# Sheet4.net
KiCad netlist of a schematic drawn in Altium Designer
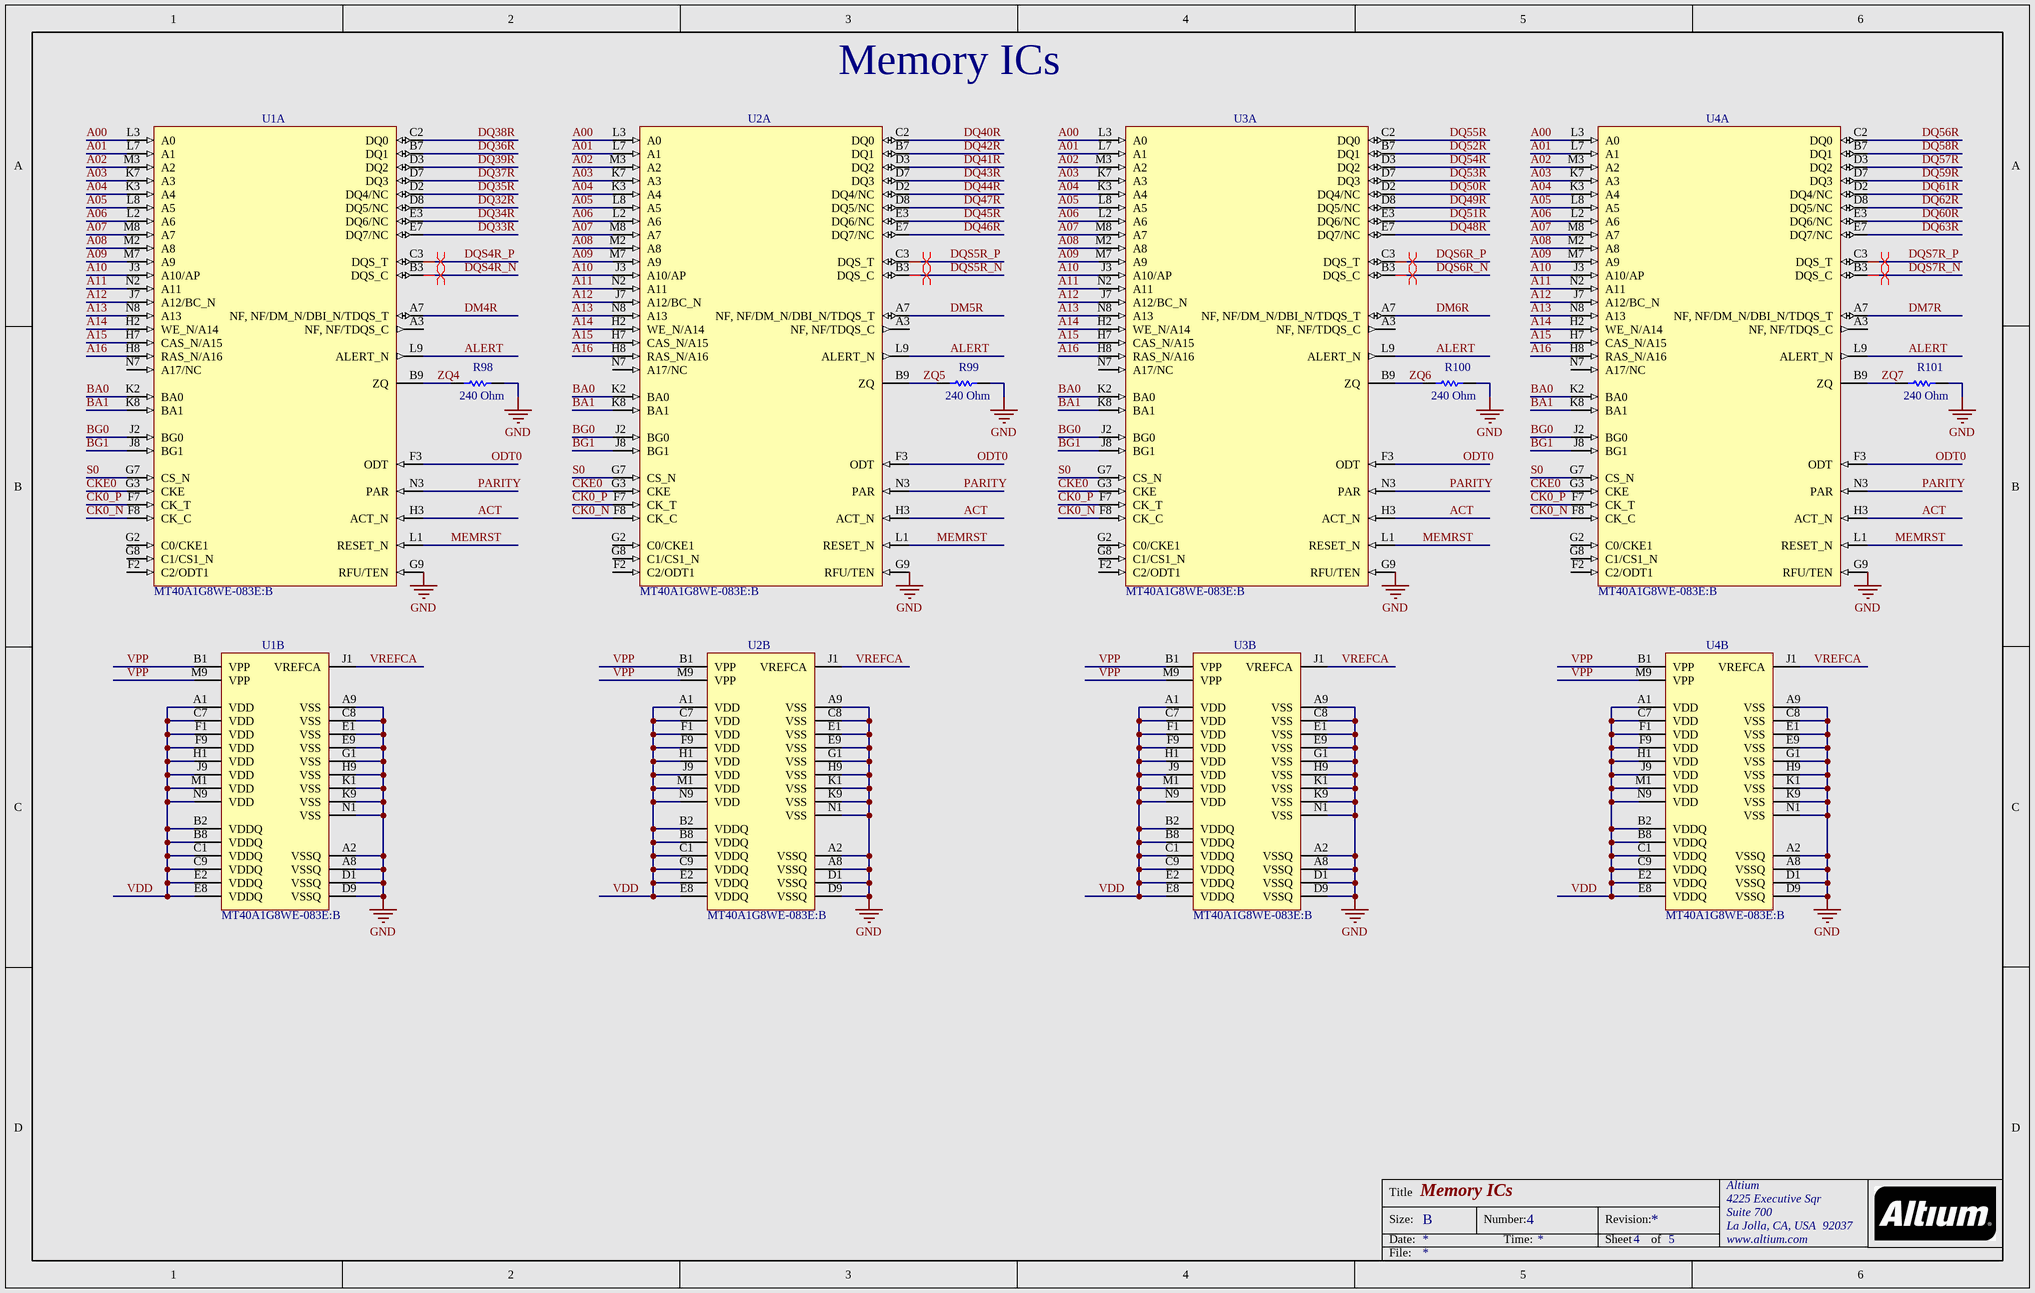
[diagram p0: Sheet4.SchDoc]

(export (version "E")
  (design (tool "Eeschema 10.0.6"))
  (components
    (comp (ref "R98")
      (value "ERJ-2GEJ241x")
      (footprint "RESC1005X40X25ML05T05")
      (description "Chip Resistor, 240 Ohm, +/- 5%, 100 mW, -55 to 155 degC, 0402 (1005 Metric), RoHS, Tape and Reel")
      (fields
        (field (name "RESISTANCE") "240 Ohm")
        (field (name "TOLERANCE") "5%")
        (field (name "MANUFACTURER") "Basic Passives")
      )
      (libsource (lib "Altium Content Vault") (part "CMP-2002-00493-3"))
    )
    (comp (ref "R99")
      (value "ERJ-2GEJ241x")
      (footprint "RESC1005X40X25ML05T05")
      (description "Chip Resistor, 240 Ohm, +/- 5%, 100 mW, -55 to 155 degC, 0402 (1005 Metric), RoHS, Tape and Reel")
      (fields
        (field (name "RESISTANCE") "240 Ohm")
        (field (name "TOLERANCE") "5%")
        (field (name "MANUFACTURER") "Basic Passives")
      )
      (libsource (lib "Altium Content Vault") (part "CMP-2002-00493-3"))
    )
    (comp (ref "R100")
      (value "ERJ-2GEJ241x")
      (footprint "RESC1005X40X25ML05T05")
      (description "Chip Resistor, 240 Ohm, +/- 5%, 100 mW, -55 to 155 degC, 0402 (1005 Metric), RoHS, Tape and Reel")
      (fields
        (field (name "RESISTANCE") "240 Ohm")
        (field (name "TOLERANCE") "5%")
        (field (name "MANUFACTURER") "Basic Passives")
      )
      (libsource (lib "Altium Content Vault") (part "CMP-2002-00493-3"))
    )
    (comp (ref "R101")
      (value "ERJ-2GEJ241x")
      (footprint "RESC1005X40X25ML05T05")
      (description "Chip Resistor, 240 Ohm, +/- 5%, 100 mW, -55 to 155 degC, 0402 (1005 Metric), RoHS, Tape and Reel")
      (fields
        (field (name "RESISTANCE") "240 Ohm")
        (field (name "TOLERANCE") "5%")
        (field (name "MANUFACTURER") "Basic Passives")
      )
      (libsource (lib "Altium Content Vault") (part "CMP-2002-00493-3"))
    )
    (comp (ref "U1")
      (value "MT40A1G8WE-083E:B")
      (footprint "MICT-WE-78")
      (description "8 Gb DDR4 SDRAM, 1 Gig x 8, 1.2 V, 0 to 95 degC, 78-Ball FBGA (WE), RoHS")
      (libsource (lib "Altium Content Vault") (part "CMP-1738-00001-1"))
    )
    (comp (ref "U2")
      (value "MT40A1G8WE-083E:B")
      (footprint "MICT-WE-78")
      (description "8 Gb DDR4 SDRAM, 1 Gig x 8, 1.2 V, 0 to 95 degC, 78-Ball FBGA (WE), RoHS")
      (libsource (lib "Altium Content Vault") (part "CMP-1738-00001-1"))
    )
    (comp (ref "U3")
      (value "MT40A1G8WE-083E:B")
      (footprint "MICT-WE-78")
      (description "8 Gb DDR4 SDRAM, 1 Gig x 8, 1.2 V, 0 to 95 degC, 78-Ball FBGA (WE), RoHS")
      (libsource (lib "Altium Content Vault") (part "CMP-1738-00001-1"))
    )
    (comp (ref "U4")
      (value "MT40A1G8WE-083E:B")
      (footprint "MICT-WE-78")
      (description "8 Gb DDR4 SDRAM, 1 Gig x 8, 1.2 V, 0 to 95 degC, 78-Ball FBGA (WE), RoHS")
      (libsource (lib "Altium Content Vault") (part "CMP-1738-00001-1"))
    )
  )
  (nets
    (net (code "1") (name "/A00") (class "Default")
      (node (ref "U1") (pin "L3") (pinfunction "A0_L3") (pintype "input"))
      (node (ref "U2") (pin "L3") (pinfunction "A0_L3") (pintype "input"))
      (node (ref "U3") (pin "L3") (pinfunction "A0_L3") (pintype "input"))
      (node (ref "U4") (pin "L3") (pinfunction "A0_L3") (pintype "input"))
    )
    (net (code "2") (name "/A01") (class "Default")
      (node (ref "U1") (pin "L7") (pinfunction "A1_L7") (pintype "input"))
      (node (ref "U2") (pin "L7") (pinfunction "A1_L7") (pintype "input"))
      (node (ref "U3") (pin "L7") (pinfunction "A1_L7") (pintype "input"))
      (node (ref "U4") (pin "L7") (pinfunction "A1_L7") (pintype "input"))
    )
    (net (code "3") (name "/A02") (class "Default")
      (node (ref "U1") (pin "M3") (pinfunction "A2_M3") (pintype "input"))
      (node (ref "U2") (pin "M3") (pinfunction "A2_M3") (pintype "input"))
      (node (ref "U3") (pin "M3") (pinfunction "A2_M3") (pintype "input"))
      (node (ref "U4") (pin "M3") (pinfunction "A2_M3") (pintype "input"))
    )
    (net (code "4") (name "/A03") (class "Default")
      (node (ref "U1") (pin "K7") (pinfunction "A3_K7") (pintype "input"))
      (node (ref "U2") (pin "K7") (pinfunction "A3_K7") (pintype "input"))
      (node (ref "U3") (pin "K7") (pinfunction "A3_K7") (pintype "input"))
      (node (ref "U4") (pin "K7") (pinfunction "A3_K7") (pintype "input"))
    )
    (net (code "5") (name "/A04") (class "Default")
      (node (ref "U1") (pin "K3") (pinfunction "A4_K3") (pintype "input"))
      (node (ref "U2") (pin "K3") (pinfunction "A4_K3") (pintype "input"))
      (node (ref "U3") (pin "K3") (pinfunction "A4_K3") (pintype "input"))
      (node (ref "U4") (pin "K3") (pinfunction "A4_K3") (pintype "input"))
    )
    (net (code "6") (name "/A05") (class "Default")
      (node (ref "U1") (pin "L8") (pinfunction "A5_L8") (pintype "input"))
      (node (ref "U2") (pin "L8") (pinfunction "A5_L8") (pintype "input"))
      (node (ref "U3") (pin "L8") (pinfunction "A5_L8") (pintype "input"))
      (node (ref "U4") (pin "L8") (pinfunction "A5_L8") (pintype "input"))
    )
    (net (code "7") (name "/A06") (class "Default")
      (node (ref "U1") (pin "L2") (pinfunction "A6_L2") (pintype "input"))
      (node (ref "U2") (pin "L2") (pinfunction "A6_L2") (pintype "input"))
      (node (ref "U3") (pin "L2") (pinfunction "A6_L2") (pintype "input"))
      (node (ref "U4") (pin "L2") (pinfunction "A6_L2") (pintype "input"))
    )
    (net (code "8") (name "/A07") (class "Default")
      (node (ref "U1") (pin "M8") (pinfunction "A7_M8") (pintype "input"))
      (node (ref "U2") (pin "M8") (pinfunction "A7_M8") (pintype "input"))
      (node (ref "U3") (pin "M8") (pinfunction "A7_M8") (pintype "input"))
      (node (ref "U4") (pin "M8") (pinfunction "A7_M8") (pintype "input"))
    )
    (net (code "9") (name "/A08") (class "Default")
      (node (ref "U1") (pin "M2") (pinfunction "A8_M2") (pintype "input"))
      (node (ref "U2") (pin "M2") (pinfunction "A8_M2") (pintype "input"))
      (node (ref "U3") (pin "M2") (pinfunction "A8_M2") (pintype "input"))
      (node (ref "U4") (pin "M2") (pinfunction "A8_M2") (pintype "input"))
    )
    (net (code "10") (name "/A09") (class "Default")
      (node (ref "U1") (pin "M7") (pinfunction "A9_M7") (pintype "input"))
      (node (ref "U2") (pin "M7") (pinfunction "A9_M7") (pintype "input"))
      (node (ref "U3") (pin "M7") (pinfunction "A9_M7") (pintype "input"))
      (node (ref "U4") (pin "M7") (pinfunction "A9_M7") (pintype "input"))
    )
    (net (code "11") (name "/A10") (class "Default")
      (node (ref "U1") (pin "J3") (pinfunction "A10/AP_J3") (pintype "input"))
      (node (ref "U2") (pin "J3") (pinfunction "A10/AP_J3") (pintype "input"))
      (node (ref "U3") (pin "J3") (pinfunction "A10/AP_J3") (pintype "input"))
      (node (ref "U4") (pin "J3") (pinfunction "A10/AP_J3") (pintype "input"))
    )
    (net (code "12") (name "/A11") (class "Default")
      (node (ref "U1") (pin "N2") (pinfunction "A11_N2") (pintype "input"))
      (node (ref "U2") (pin "N2") (pinfunction "A11_N2") (pintype "input"))
      (node (ref "U3") (pin "N2") (pinfunction "A11_N2") (pintype "input"))
      (node (ref "U4") (pin "N2") (pinfunction "A11_N2") (pintype "input"))
    )
    (net (code "13") (name "/A12") (class "Default")
      (node (ref "U1") (pin "J7") (pinfunction "A12/BC_N_J7") (pintype "input"))
      (node (ref "U2") (pin "J7") (pinfunction "A12/BC_N_J7") (pintype "input"))
      (node (ref "U3") (pin "J7") (pinfunction "A12/BC_N_J7") (pintype "input"))
      (node (ref "U4") (pin "J7") (pinfunction "A12/BC_N_J7") (pintype "input"))
    )
    (net (code "14") (name "/A13") (class "Default")
      (node (ref "U1") (pin "N8") (pinfunction "A13_N8") (pintype "input"))
      (node (ref "U2") (pin "N8") (pinfunction "A13_N8") (pintype "input"))
      (node (ref "U3") (pin "N8") (pinfunction "A13_N8") (pintype "input"))
      (node (ref "U4") (pin "N8") (pinfunction "A13_N8") (pintype "input"))
    )
    (net (code "15") (name "/A14") (class "Default")
      (node (ref "U1") (pin "H2") (pinfunction "WE_N/A14_H2") (pintype "input"))
      (node (ref "U2") (pin "H2") (pinfunction "WE_N/A14_H2") (pintype "input"))
      (node (ref "U3") (pin "H2") (pinfunction "WE_N/A14_H2") (pintype "input"))
      (node (ref "U4") (pin "H2") (pinfunction "WE_N/A14_H2") (pintype "input"))
    )
    (net (code "16") (name "/A15") (class "Default")
      (node (ref "U1") (pin "H7") (pinfunction "CAS_N/A15_H7") (pintype "input"))
      (node (ref "U2") (pin "H7") (pinfunction "CAS_N/A15_H7") (pintype "input"))
      (node (ref "U3") (pin "H7") (pinfunction "CAS_N/A15_H7") (pintype "input"))
      (node (ref "U4") (pin "H7") (pinfunction "CAS_N/A15_H7") (pintype "input"))
    )
    (net (code "17") (name "/A16") (class "Default")
      (node (ref "U1") (pin "H8") (pinfunction "RAS_N/A16_H8") (pintype "input"))
      (node (ref "U2") (pin "H8") (pinfunction "RAS_N/A16_H8") (pintype "input"))
      (node (ref "U3") (pin "H8") (pinfunction "RAS_N/A16_H8") (pintype "input"))
      (node (ref "U4") (pin "H8") (pinfunction "RAS_N/A16_H8") (pintype "input"))
    )
    (net (code "18") (name "/ACT") (class "Default")
      (node (ref "U1") (pin "H3") (pinfunction "ACT_N_H3") (pintype "input"))
      (node (ref "U2") (pin "H3") (pinfunction "ACT_N_H3") (pintype "input"))
      (node (ref "U3") (pin "H3") (pinfunction "ACT_N_H3") (pintype "input"))
      (node (ref "U4") (pin "H3") (pinfunction "ACT_N_H3") (pintype "input"))
    )
    (net (code "19") (name "/ALERT") (class "Default")
      (node (ref "U1") (pin "L9") (pinfunction "ALERT_N_L9") (pintype "output"))
      (node (ref "U2") (pin "L9") (pinfunction "ALERT_N_L9") (pintype "output"))
      (node (ref "U3") (pin "L9") (pinfunction "ALERT_N_L9") (pintype "output"))
      (node (ref "U4") (pin "L9") (pinfunction "ALERT_N_L9") (pintype "output"))
    )
    (net (code "20") (name "/BA0") (class "Default")
      (node (ref "U1") (pin "K2") (pinfunction "BA0_K2") (pintype "input"))
      (node (ref "U2") (pin "K2") (pinfunction "BA0_K2") (pintype "input"))
      (node (ref "U3") (pin "K2") (pinfunction "BA0_K2") (pintype "input"))
      (node (ref "U4") (pin "K2") (pinfunction "BA0_K2") (pintype "input"))
    )
    (net (code "21") (name "/BA1") (class "Default")
      (node (ref "U1") (pin "K8") (pinfunction "BA1_K8") (pintype "input"))
      (node (ref "U2") (pin "K8") (pinfunction "BA1_K8") (pintype "input"))
      (node (ref "U3") (pin "K8") (pinfunction "BA1_K8") (pintype "input"))
      (node (ref "U4") (pin "K8") (pinfunction "BA1_K8") (pintype "input"))
    )
    (net (code "22") (name "/BG0") (class "Default")
      (node (ref "U1") (pin "J2") (pinfunction "BG0_J2") (pintype "input"))
      (node (ref "U2") (pin "J2") (pinfunction "BG0_J2") (pintype "input"))
      (node (ref "U3") (pin "J2") (pinfunction "BG0_J2") (pintype "input"))
      (node (ref "U4") (pin "J2") (pinfunction "BG0_J2") (pintype "input"))
    )
    (net (code "23") (name "/BG1") (class "Default")
      (node (ref "U1") (pin "J8") (pinfunction "BG1_J8") (pintype "input"))
      (node (ref "U2") (pin "J8") (pinfunction "BG1_J8") (pintype "input"))
      (node (ref "U3") (pin "J8") (pinfunction "BG1_J8") (pintype "input"))
      (node (ref "U4") (pin "J8") (pinfunction "BG1_J8") (pintype "input"))
    )
    (net (code "24") (name "/CK0_N") (class "Default")
      (node (ref "U1") (pin "F8") (pinfunction "CK_C_F8") (pintype "input"))
      (node (ref "U2") (pin "F8") (pinfunction "CK_C_F8") (pintype "input"))
      (node (ref "U3") (pin "F8") (pinfunction "CK_C_F8") (pintype "input"))
      (node (ref "U4") (pin "F8") (pinfunction "CK_C_F8") (pintype "input"))
    )
    (net (code "25") (name "/CK0_P") (class "Default")
      (node (ref "U1") (pin "F7") (pinfunction "CK_T_F7") (pintype "input"))
      (node (ref "U2") (pin "F7") (pinfunction "CK_T_F7") (pintype "input"))
      (node (ref "U3") (pin "F7") (pinfunction "CK_T_F7") (pintype "input"))
      (node (ref "U4") (pin "F7") (pinfunction "CK_T_F7") (pintype "input"))
    )
    (net (code "26") (name "/CKE0") (class "Default")
      (node (ref "U1") (pin "G3") (pinfunction "CKE_G3") (pintype "input"))
      (node (ref "U2") (pin "G3") (pinfunction "CKE_G3") (pintype "input"))
      (node (ref "U3") (pin "G3") (pinfunction "CKE_G3") (pintype "input"))
      (node (ref "U4") (pin "G3") (pinfunction "CKE_G3") (pintype "input"))
    )
    (net (code "27") (name "/DM4R") (class "Default")
      (node (ref "U1") (pin "A7") (pinfunction "NF,_NF/DM_N/DBI_N/TDQS_T_A7") (pintype "bidirectional"))
    )
    (net (code "28") (name "/DM5R") (class "Default")
      (node (ref "U2") (pin "A7") (pinfunction "NF,_NF/DM_N/DBI_N/TDQS_T_A7") (pintype "bidirectional"))
    )
    (net (code "29") (name "/DM6R") (class "Default")
      (node (ref "U3") (pin "A7") (pinfunction "NF,_NF/DM_N/DBI_N/TDQS_T_A7") (pintype "bidirectional"))
    )
    (net (code "30") (name "/DM7R") (class "Default")
      (node (ref "U4") (pin "A7") (pinfunction "NF,_NF/DM_N/DBI_N/TDQS_T_A7") (pintype "bidirectional"))
    )
    (net (code "31") (name "/DQ32R") (class "Default")
      (node (ref "U1") (pin "D8") (pinfunction "DQ5/NC_D8") (pintype "bidirectional"))
    )
    (net (code "32") (name "/DQ33R") (class "Default")
      (node (ref "U1") (pin "E7") (pinfunction "DQ7/NC_E7") (pintype "bidirectional"))
    )
    (net (code "33") (name "/DQ34R") (class "Default")
      (node (ref "U1") (pin "E3") (pinfunction "DQ6/NC_E3") (pintype "bidirectional"))
    )
    (net (code "34") (name "/DQ35R") (class "Default")
      (node (ref "U1") (pin "D2") (pinfunction "DQ4/NC_D2") (pintype "bidirectional"))
    )
    (net (code "35") (name "/DQ36R") (class "Default")
      (node (ref "U1") (pin "B7") (pinfunction "DQ1_B7") (pintype "bidirectional"))
    )
    (net (code "36") (name "/DQ37R") (class "Default")
      (node (ref "U1") (pin "D7") (pinfunction "DQ3_D7") (pintype "bidirectional"))
    )
    (net (code "37") (name "/DQ38R") (class "Default")
      (node (ref "U1") (pin "C2") (pinfunction "DQ0_C2") (pintype "bidirectional"))
    )
    (net (code "38") (name "/DQ39R") (class "Default")
      (node (ref "U1") (pin "D3") (pinfunction "DQ2_D3") (pintype "bidirectional"))
    )
    (net (code "39") (name "/DQ40R") (class "Default")
      (node (ref "U2") (pin "C2") (pinfunction "DQ0_C2") (pintype "bidirectional"))
    )
    (net (code "40") (name "/DQ41R") (class "Default")
      (node (ref "U2") (pin "D3") (pinfunction "DQ2_D3") (pintype "bidirectional"))
    )
    (net (code "41") (name "/DQ42R") (class "Default")
      (node (ref "U2") (pin "B7") (pinfunction "DQ1_B7") (pintype "bidirectional"))
    )
    (net (code "42") (name "/DQ43R") (class "Default")
      (node (ref "U2") (pin "D7") (pinfunction "DQ3_D7") (pintype "bidirectional"))
    )
    (net (code "43") (name "/DQ44R") (class "Default")
      (node (ref "U2") (pin "D2") (pinfunction "DQ4/NC_D2") (pintype "bidirectional"))
    )
    (net (code "44") (name "/DQ45R") (class "Default")
      (node (ref "U2") (pin "E3") (pinfunction "DQ6/NC_E3") (pintype "bidirectional"))
    )
    (net (code "45") (name "/DQ46R") (class "Default")
      (node (ref "U2") (pin "E7") (pinfunction "DQ7/NC_E7") (pintype "bidirectional"))
    )
    (net (code "46") (name "/DQ47R") (class "Default")
      (node (ref "U2") (pin "D8") (pinfunction "DQ5/NC_D8") (pintype "bidirectional"))
    )
    (net (code "47") (name "/DQ48R") (class "Default")
      (node (ref "U3") (pin "E7") (pinfunction "DQ7/NC_E7") (pintype "bidirectional"))
    )
    (net (code "48") (name "/DQ49R") (class "Default")
      (node (ref "U3") (pin "D8") (pinfunction "DQ5/NC_D8") (pintype "bidirectional"))
    )
    (net (code "49") (name "/DQ50R") (class "Default")
      (node (ref "U3") (pin "D2") (pinfunction "DQ4/NC_D2") (pintype "bidirectional"))
    )
    (net (code "50") (name "/DQ51R") (class "Default")
      (node (ref "U3") (pin "E3") (pinfunction "DQ6/NC_E3") (pintype "bidirectional"))
    )
    (net (code "51") (name "/DQ52R") (class "Default")
      (node (ref "U3") (pin "B7") (pinfunction "DQ1_B7") (pintype "bidirectional"))
    )
    (net (code "52") (name "/DQ53R") (class "Default")
      (node (ref "U3") (pin "D7") (pinfunction "DQ3_D7") (pintype "bidirectional"))
    )
    (net (code "53") (name "/DQ54R") (class "Default")
      (node (ref "U3") (pin "D3") (pinfunction "DQ2_D3") (pintype "bidirectional"))
    )
    (net (code "54") (name "/DQ55R") (class "Default")
      (node (ref "U3") (pin "C2") (pinfunction "DQ0_C2") (pintype "bidirectional"))
    )
    (net (code "55") (name "/DQ56R") (class "Default")
      (node (ref "U4") (pin "C2") (pinfunction "DQ0_C2") (pintype "bidirectional"))
    )
    (net (code "56") (name "/DQ57R") (class "Default")
      (node (ref "U4") (pin "D3") (pinfunction "DQ2_D3") (pintype "bidirectional"))
    )
    (net (code "57") (name "/DQ58R") (class "Default")
      (node (ref "U4") (pin "B7") (pinfunction "DQ1_B7") (pintype "bidirectional"))
    )
    (net (code "58") (name "/DQ59R") (class "Default")
      (node (ref "U4") (pin "D7") (pinfunction "DQ3_D7") (pintype "bidirectional"))
    )
    (net (code "59") (name "/DQ60R") (class "Default")
      (node (ref "U4") (pin "E3") (pinfunction "DQ6/NC_E3") (pintype "bidirectional"))
    )
    (net (code "60") (name "/DQ61R") (class "Default")
      (node (ref "U4") (pin "D2") (pinfunction "DQ4/NC_D2") (pintype "bidirectional"))
    )
    (net (code "61") (name "/DQ62R") (class "Default")
      (node (ref "U4") (pin "D8") (pinfunction "DQ5/NC_D8") (pintype "bidirectional"))
    )
    (net (code "62") (name "/DQ63R") (class "Default")
      (node (ref "U4") (pin "E7") (pinfunction "DQ7/NC_E7") (pintype "bidirectional"))
    )
    (net (code "63") (name "/DQS4R_N") (class "Default")
      (node (ref "U1") (pin "B3") (pinfunction "DQS_C_B3") (pintype "bidirectional"))
    )
    (net (code "64") (name "/DQS4R_P") (class "Default")
      (node (ref "U1") (pin "C3") (pinfunction "DQS_T_C3") (pintype "bidirectional"))
    )
    (net (code "65") (name "/DQS5R_N") (class "Default")
      (node (ref "U2") (pin "B3") (pinfunction "DQS_C_B3") (pintype "bidirectional"))
    )
    (net (code "66") (name "/DQS5R_P") (class "Default")
      (node (ref "U2") (pin "C3") (pinfunction "DQS_T_C3") (pintype "bidirectional"))
    )
    (net (code "67") (name "/DQS6R_N") (class "Default")
      (node (ref "U3") (pin "B3") (pinfunction "DQS_C_B3") (pintype "bidirectional"))
    )
    (net (code "68") (name "/DQS6R_P") (class "Default")
      (node (ref "U3") (pin "C3") (pinfunction "DQS_T_C3") (pintype "bidirectional"))
    )
    (net (code "69") (name "/DQS7R_N") (class "Default")
      (node (ref "U4") (pin "B3") (pinfunction "DQS_C_B3") (pintype "bidirectional"))
    )
    (net (code "70") (name "/DQS7R_P") (class "Default")
      (node (ref "U4") (pin "C3") (pinfunction "DQS_T_C3") (pintype "bidirectional"))
    )
    (net (code "71") (name "/MEMRST") (class "Default")
      (node (ref "U1") (pin "L1") (pinfunction "RESET_N_L1") (pintype "input"))
      (node (ref "U2") (pin "L1") (pinfunction "RESET_N_L1") (pintype "input"))
      (node (ref "U3") (pin "L1") (pinfunction "RESET_N_L1") (pintype "input"))
      (node (ref "U4") (pin "L1") (pinfunction "RESET_N_L1") (pintype "input"))
    )
    (net (code "72") (name "/ODT0") (class "Default")
      (node (ref "U1") (pin "F3") (pinfunction "ODT_F3") (pintype "input"))
      (node (ref "U2") (pin "F3") (pinfunction "ODT_F3") (pintype "input"))
      (node (ref "U3") (pin "F3") (pinfunction "ODT_F3") (pintype "input"))
      (node (ref "U4") (pin "F3") (pinfunction "ODT_F3") (pintype "input"))
    )
    (net (code "73") (name "/PARITY") (class "Default")
      (node (ref "U1") (pin "N3") (pinfunction "PAR_N3") (pintype "input"))
      (node (ref "U2") (pin "N3") (pinfunction "PAR_N3") (pintype "input"))
      (node (ref "U3") (pin "N3") (pinfunction "PAR_N3") (pintype "input"))
      (node (ref "U4") (pin "N3") (pinfunction "PAR_N3") (pintype "input"))
    )
    (net (code "74") (name "/S0") (class "Default")
      (node (ref "U1") (pin "G7") (pinfunction "CS_N_G7") (pintype "input"))
      (node (ref "U2") (pin "G7") (pinfunction "CS_N_G7") (pintype "input"))
      (node (ref "U3") (pin "G7") (pinfunction "CS_N_G7") (pintype "input"))
      (node (ref "U4") (pin "G7") (pinfunction "CS_N_G7") (pintype "input"))
    )
    (net (code "75") (name "/VDD") (class "Default")
      (node (ref "U1") (pin "A1") (pinfunction "VDD_A1") (pintype "power_in"))
      (node (ref "U1") (pin "B2") (pinfunction "VDDQ_B2") (pintype "power_in"))
      (node (ref "U1") (pin "B8") (pinfunction "VDDQ_B8") (pintype "power_in"))
      (node (ref "U1") (pin "C1") (pinfunction "VDDQ_C1") (pintype "power_in"))
      (node (ref "U1") (pin "C7") (pinfunction "VDD_C7") (pintype "power_in"))
      (node (ref "U1") (pin "C9") (pinfunction "VDDQ_C9") (pintype "power_in"))
      (node (ref "U1") (pin "E2") (pinfunction "VDDQ_E2") (pintype "power_in"))
      (node (ref "U1") (pin "E8") (pinfunction "VDDQ_E8") (pintype "power_in"))
      (node (ref "U1") (pin "F1") (pinfunction "VDD_F1") (pintype "power_in"))
      (node (ref "U1") (pin "F9") (pinfunction "VDD_F9") (pintype "power_in"))
      (node (ref "U1") (pin "H1") (pinfunction "VDD_H1") (pintype "power_in"))
      (node (ref "U1") (pin "J9") (pinfunction "VDD_J9") (pintype "power_in"))
      (node (ref "U1") (pin "M1") (pinfunction "VDD_M1") (pintype "power_in"))
      (node (ref "U1") (pin "N9") (pinfunction "VDD_N9") (pintype "power_in"))
      (node (ref "U2") (pin "A1") (pinfunction "VDD_A1") (pintype "power_in"))
      (node (ref "U2") (pin "B2") (pinfunction "VDDQ_B2") (pintype "power_in"))
      (node (ref "U2") (pin "B8") (pinfunction "VDDQ_B8") (pintype "power_in"))
      (node (ref "U2") (pin "C1") (pinfunction "VDDQ_C1") (pintype "power_in"))
      (node (ref "U2") (pin "C7") (pinfunction "VDD_C7") (pintype "power_in"))
      (node (ref "U2") (pin "C9") (pinfunction "VDDQ_C9") (pintype "power_in"))
      (node (ref "U2") (pin "E2") (pinfunction "VDDQ_E2") (pintype "power_in"))
      (node (ref "U2") (pin "E8") (pinfunction "VDDQ_E8") (pintype "power_in"))
      (node (ref "U2") (pin "F1") (pinfunction "VDD_F1") (pintype "power_in"))
      (node (ref "U2") (pin "F9") (pinfunction "VDD_F9") (pintype "power_in"))
      (node (ref "U2") (pin "H1") (pinfunction "VDD_H1") (pintype "power_in"))
      (node (ref "U2") (pin "J9") (pinfunction "VDD_J9") (pintype "power_in"))
      (node (ref "U2") (pin "M1") (pinfunction "VDD_M1") (pintype "power_in"))
      (node (ref "U2") (pin "N9") (pinfunction "VDD_N9") (pintype "power_in"))
      (node (ref "U3") (pin "A1") (pinfunction "VDD_A1") (pintype "power_in"))
      (node (ref "U3") (pin "B2") (pinfunction "VDDQ_B2") (pintype "power_in"))
      (node (ref "U3") (pin "B8") (pinfunction "VDDQ_B8") (pintype "power_in"))
      (node (ref "U3") (pin "C1") (pinfunction "VDDQ_C1") (pintype "power_in"))
      (node (ref "U3") (pin "C7") (pinfunction "VDD_C7") (pintype "power_in"))
      (node (ref "U3") (pin "C9") (pinfunction "VDDQ_C9") (pintype "power_in"))
      (node (ref "U3") (pin "E2") (pinfunction "VDDQ_E2") (pintype "power_in"))
      (node (ref "U3") (pin "E8") (pinfunction "VDDQ_E8") (pintype "power_in"))
      (node (ref "U3") (pin "F1") (pinfunction "VDD_F1") (pintype "power_in"))
      (node (ref "U3") (pin "F9") (pinfunction "VDD_F9") (pintype "power_in"))
      (node (ref "U3") (pin "H1") (pinfunction "VDD_H1") (pintype "power_in"))
      (node (ref "U3") (pin "J9") (pinfunction "VDD_J9") (pintype "power_in"))
      (node (ref "U3") (pin "M1") (pinfunction "VDD_M1") (pintype "power_in"))
      (node (ref "U3") (pin "N9") (pinfunction "VDD_N9") (pintype "power_in"))
      (node (ref "U4") (pin "A1") (pinfunction "VDD_A1") (pintype "power_in"))
      (node (ref "U4") (pin "B2") (pinfunction "VDDQ_B2") (pintype "power_in"))
      (node (ref "U4") (pin "B8") (pinfunction "VDDQ_B8") (pintype "power_in"))
      (node (ref "U4") (pin "C1") (pinfunction "VDDQ_C1") (pintype "power_in"))
      (node (ref "U4") (pin "C7") (pinfunction "VDD_C7") (pintype "power_in"))
      (node (ref "U4") (pin "C9") (pinfunction "VDDQ_C9") (pintype "power_in"))
      (node (ref "U4") (pin "E2") (pinfunction "VDDQ_E2") (pintype "power_in"))
      (node (ref "U4") (pin "E8") (pinfunction "VDDQ_E8") (pintype "power_in"))
      (node (ref "U4") (pin "F1") (pinfunction "VDD_F1") (pintype "power_in"))
      (node (ref "U4") (pin "F9") (pinfunction "VDD_F9") (pintype "power_in"))
      (node (ref "U4") (pin "H1") (pinfunction "VDD_H1") (pintype "power_in"))
      (node (ref "U4") (pin "J9") (pinfunction "VDD_J9") (pintype "power_in"))
      (node (ref "U4") (pin "M1") (pinfunction "VDD_M1") (pintype "power_in"))
      (node (ref "U4") (pin "N9") (pinfunction "VDD_N9") (pintype "power_in"))
    )
    (net (code "76") (name "/VPP") (class "Default")
      (node (ref "U1") (pin "B1") (pinfunction "VPP_B1") (pintype "power_in"))
      (node (ref "U1") (pin "M9") (pinfunction "VPP_M9") (pintype "power_in"))
      (node (ref "U2") (pin "B1") (pinfunction "VPP_B1") (pintype "power_in"))
      (node (ref "U2") (pin "M9") (pinfunction "VPP_M9") (pintype "power_in"))
      (node (ref "U3") (pin "B1") (pinfunction "VPP_B1") (pintype "power_in"))
      (node (ref "U3") (pin "M9") (pinfunction "VPP_M9") (pintype "power_in"))
      (node (ref "U4") (pin "B1") (pinfunction "VPP_B1") (pintype "power_in"))
      (node (ref "U4") (pin "M9") (pinfunction "VPP_M9") (pintype "power_in"))
    )
    (net (code "77") (name "/VREFCA") (class "Default")
      (node (ref "U1") (pin "J1") (pinfunction "VREFCA_J1") (pintype "passive"))
      (node (ref "U2") (pin "J1") (pinfunction "VREFCA_J1") (pintype "passive"))
      (node (ref "U3") (pin "J1") (pinfunction "VREFCA_J1") (pintype "passive"))
      (node (ref "U4") (pin "J1") (pinfunction "VREFCA_J1") (pintype "passive"))
    )
    (net (code "78") (name "/ZQ4") (class "Default")
      (node (ref "R98") (pin "2") (pinfunction "2_2") (pintype "passive"))
      (node (ref "U1") (pin "B9") (pinfunction "ZQ_B9") (pintype "passive"))
    )
    (net (code "79") (name "/ZQ5") (class "Default")
      (node (ref "R99") (pin "2") (pinfunction "2_2") (pintype "passive"))
      (node (ref "U2") (pin "B9") (pinfunction "ZQ_B9") (pintype "passive"))
    )
    (net (code "80") (name "/ZQ6") (class "Default")
      (node (ref "R100") (pin "2") (pinfunction "2_2") (pintype "passive"))
      (node (ref "U3") (pin "B9") (pinfunction "ZQ_B9") (pintype "passive"))
    )
    (net (code "81") (name "/ZQ7") (class "Default")
      (node (ref "R101") (pin "2") (pinfunction "2_2") (pintype "passive"))
      (node (ref "U4") (pin "B9") (pinfunction "ZQ_B9") (pintype "passive"))
    )
    (net (code "82") (name "GND") (class "Default")
      (node (ref "R100") (pin "1") (pinfunction "1_1") (pintype "passive"))
      (node (ref "R101") (pin "1") (pinfunction "1_1") (pintype "passive"))
      (node (ref "R98") (pin "1") (pinfunction "1_1") (pintype "passive"))
      (node (ref "R99") (pin "1") (pinfunction "1_1") (pintype "passive"))
      (node (ref "U1") (pin "A2") (pinfunction "VSSQ_A2") (pintype "power_in"))
      (node (ref "U1") (pin "A8") (pinfunction "VSSQ_A8") (pintype "power_in"))
      (node (ref "U1") (pin "A9") (pinfunction "VSS_A9") (pintype "power_in"))
      (node (ref "U1") (pin "C8") (pinfunction "VSS_C8") (pintype "power_in"))
      (node (ref "U1") (pin "D1") (pinfunction "VSSQ_D1") (pintype "power_in"))
      (node (ref "U1") (pin "D9") (pinfunction "VSSQ_D9") (pintype "power_in"))
      (node (ref "U1") (pin "E1") (pinfunction "VSS_E1") (pintype "power_in"))
      (node (ref "U1") (pin "E9") (pinfunction "VSS_E9") (pintype "power_in"))
      (node (ref "U1") (pin "G1") (pinfunction "VSS_G1") (pintype "power_in"))
      (node (ref "U1") (pin "G9") (pinfunction "RFU/TEN_G9") (pintype "input"))
      (node (ref "U1") (pin "H9") (pinfunction "VSS_H9") (pintype "power_in"))
      (node (ref "U1") (pin "K1") (pinfunction "VSS_K1") (pintype "power_in"))
      (node (ref "U1") (pin "K9") (pinfunction "VSS_K9") (pintype "power_in"))
      (node (ref "U1") (pin "N1") (pinfunction "VSS_N1") (pintype "power_in"))
      (node (ref "U2") (pin "A2") (pinfunction "VSSQ_A2") (pintype "power_in"))
      (node (ref "U2") (pin "A8") (pinfunction "VSSQ_A8") (pintype "power_in"))
      (node (ref "U2") (pin "A9") (pinfunction "VSS_A9") (pintype "power_in"))
      (node (ref "U2") (pin "C8") (pinfunction "VSS_C8") (pintype "power_in"))
      (node (ref "U2") (pin "D1") (pinfunction "VSSQ_D1") (pintype "power_in"))
      (node (ref "U2") (pin "D9") (pinfunction "VSSQ_D9") (pintype "power_in"))
      (node (ref "U2") (pin "E1") (pinfunction "VSS_E1") (pintype "power_in"))
      (node (ref "U2") (pin "E9") (pinfunction "VSS_E9") (pintype "power_in"))
      (node (ref "U2") (pin "G1") (pinfunction "VSS_G1") (pintype "power_in"))
      (node (ref "U2") (pin "G9") (pinfunction "RFU/TEN_G9") (pintype "input"))
      (node (ref "U2") (pin "H9") (pinfunction "VSS_H9") (pintype "power_in"))
      (node (ref "U2") (pin "K1") (pinfunction "VSS_K1") (pintype "power_in"))
      (node (ref "U2") (pin "K9") (pinfunction "VSS_K9") (pintype "power_in"))
      (node (ref "U2") (pin "N1") (pinfunction "VSS_N1") (pintype "power_in"))
      (node (ref "U3") (pin "A2") (pinfunction "VSSQ_A2") (pintype "power_in"))
      (node (ref "U3") (pin "A8") (pinfunction "VSSQ_A8") (pintype "power_in"))
      (node (ref "U3") (pin "A9") (pinfunction "VSS_A9") (pintype "power_in"))
      (node (ref "U3") (pin "C8") (pinfunction "VSS_C8") (pintype "power_in"))
      (node (ref "U3") (pin "D1") (pinfunction "VSSQ_D1") (pintype "power_in"))
      (node (ref "U3") (pin "D9") (pinfunction "VSSQ_D9") (pintype "power_in"))
      (node (ref "U3") (pin "E1") (pinfunction "VSS_E1") (pintype "power_in"))
      (node (ref "U3") (pin "E9") (pinfunction "VSS_E9") (pintype "power_in"))
      (node (ref "U3") (pin "G1") (pinfunction "VSS_G1") (pintype "power_in"))
      (node (ref "U3") (pin "G9") (pinfunction "RFU/TEN_G9") (pintype "input"))
      (node (ref "U3") (pin "H9") (pinfunction "VSS_H9") (pintype "power_in"))
      (node (ref "U3") (pin "K1") (pinfunction "VSS_K1") (pintype "power_in"))
      (node (ref "U3") (pin "K9") (pinfunction "VSS_K9") (pintype "power_in"))
      (node (ref "U3") (pin "N1") (pinfunction "VSS_N1") (pintype "power_in"))
      (node (ref "U4") (pin "A2") (pinfunction "VSSQ_A2") (pintype "power_in"))
      (node (ref "U4") (pin "A8") (pinfunction "VSSQ_A8") (pintype "power_in"))
      (node (ref "U4") (pin "A9") (pinfunction "VSS_A9") (pintype "power_in"))
      (node (ref "U4") (pin "C8") (pinfunction "VSS_C8") (pintype "power_in"))
      (node (ref "U4") (pin "D1") (pinfunction "VSSQ_D1") (pintype "power_in"))
      (node (ref "U4") (pin "D9") (pinfunction "VSSQ_D9") (pintype "power_in"))
      (node (ref "U4") (pin "E1") (pinfunction "VSS_E1") (pintype "power_in"))
      (node (ref "U4") (pin "E9") (pinfunction "VSS_E9") (pintype "power_in"))
      (node (ref "U4") (pin "G1") (pinfunction "VSS_G1") (pintype "power_in"))
      (node (ref "U4") (pin "G9") (pinfunction "RFU/TEN_G9") (pintype "input"))
      (node (ref "U4") (pin "H9") (pinfunction "VSS_H9") (pintype "power_in"))
      (node (ref "U4") (pin "K1") (pinfunction "VSS_K1") (pintype "power_in"))
      (node (ref "U4") (pin "K9") (pinfunction "VSS_K9") (pintype "power_in"))
      (node (ref "U4") (pin "N1") (pinfunction "VSS_N1") (pintype "power_in"))
    )
    (net (code "83") (name "unconnected-(U1A-A17{slash}NC-PadN7)") (class "Default")
      (node (ref "U1") (pin "N7") (pinfunction "A17/NC_N7") (pintype "input"))
    )
    (net (code "84") (name "unconnected-(U1A-C0{slash}CKE1-PadG2)") (class "Default")
      (node (ref "U1") (pin "G2") (pinfunction "C0/CKE1_G2") (pintype "input"))
    )
    (net (code "85") (name "unconnected-(U1A-C1{slash}CS1_N-PadG8)") (class "Default")
      (node (ref "U1") (pin "G8") (pinfunction "C1/CS1_N_G8") (pintype "input"))
    )
    (net (code "86") (name "unconnected-(U1A-C2{slash}ODT1-PadF2)") (class "Default")
      (node (ref "U1") (pin "F2") (pinfunction "C2/ODT1_F2") (pintype "input"))
    )
    (net (code "87") (name "unconnected-(U1A-NF,_NF{slash}TDQS_C-PadA3)") (class "Default")
      (node (ref "U1") (pin "A3") (pinfunction "NF,_NF/TDQS_C_A3") (pintype "output"))
    )
    (net (code "88") (name "unconnected-(U2A-A17{slash}NC-PadN7)") (class "Default")
      (node (ref "U2") (pin "N7") (pinfunction "A17/NC_N7") (pintype "input"))
    )
    (net (code "89") (name "unconnected-(U2A-C0{slash}CKE1-PadG2)") (class "Default")
      (node (ref "U2") (pin "G2") (pinfunction "C0/CKE1_G2") (pintype "input"))
    )
    (net (code "90") (name "unconnected-(U2A-C1{slash}CS1_N-PadG8)") (class "Default")
      (node (ref "U2") (pin "G8") (pinfunction "C1/CS1_N_G8") (pintype "input"))
    )
    (net (code "91") (name "unconnected-(U2A-C2{slash}ODT1-PadF2)") (class "Default")
      (node (ref "U2") (pin "F2") (pinfunction "C2/ODT1_F2") (pintype "input"))
    )
    (net (code "92") (name "unconnected-(U2A-NF,_NF{slash}TDQS_C-PadA3)") (class "Default")
      (node (ref "U2") (pin "A3") (pinfunction "NF,_NF/TDQS_C_A3") (pintype "output"))
    )
    (net (code "93") (name "unconnected-(U3A-A17{slash}NC-PadN7)") (class "Default")
      (node (ref "U3") (pin "N7") (pinfunction "A17/NC_N7") (pintype "input"))
    )
    (net (code "94") (name "unconnected-(U3A-C0{slash}CKE1-PadG2)") (class "Default")
      (node (ref "U3") (pin "G2") (pinfunction "C0/CKE1_G2") (pintype "input"))
    )
    (net (code "95") (name "unconnected-(U3A-C1{slash}CS1_N-PadG8)") (class "Default")
      (node (ref "U3") (pin "G8") (pinfunction "C1/CS1_N_G8") (pintype "input"))
    )
    (net (code "96") (name "unconnected-(U3A-C2{slash}ODT1-PadF2)") (class "Default")
      (node (ref "U3") (pin "F2") (pinfunction "C2/ODT1_F2") (pintype "input"))
    )
    (net (code "97") (name "unconnected-(U3A-NF,_NF{slash}TDQS_C-PadA3)") (class "Default")
      (node (ref "U3") (pin "A3") (pinfunction "NF,_NF/TDQS_C_A3") (pintype "output"))
    )
    (net (code "98") (name "unconnected-(U4A-A17{slash}NC-PadN7)") (class "Default")
      (node (ref "U4") (pin "N7") (pinfunction "A17/NC_N7") (pintype "input"))
    )
    (net (code "99") (name "unconnected-(U4A-C0{slash}CKE1-PadG2)") (class "Default")
      (node (ref "U4") (pin "G2") (pinfunction "C0/CKE1_G2") (pintype "input"))
    )
    (net (code "100") (name "unconnected-(U4A-C1{slash}CS1_N-PadG8)") (class "Default")
      (node (ref "U4") (pin "G8") (pinfunction "C1/CS1_N_G8") (pintype "input"))
    )
    (net (code "101") (name "unconnected-(U4A-C2{slash}ODT1-PadF2)") (class "Default")
      (node (ref "U4") (pin "F2") (pinfunction "C2/ODT1_F2") (pintype "input"))
    )
    (net (code "102") (name "unconnected-(U4A-NF,_NF{slash}TDQS_C-PadA3)") (class "Default")
      (node (ref "U4") (pin "A3") (pinfunction "NF,_NF/TDQS_C_A3") (pintype "output"))
    )
  )
)
